# sensors.net
KiCad netlist of a schematic drawn in Altium Designer
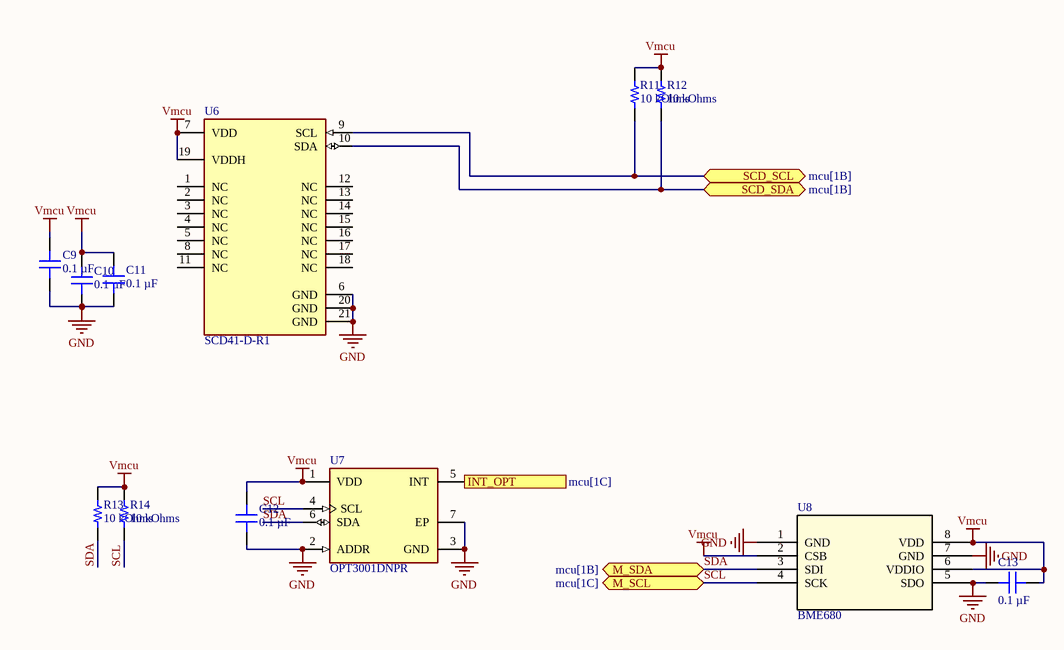
[diagram p0: sensors.SchDoc]

(export (version "E")
  (design (tool "Eeschema 10.0.6"))
  (components
    (comp (ref "C9")
      (value "0.1 µF")
      (footprint "CAP 0402_1005")
      (description "CAP CER 0.1UF 4V X5R 0402")
      (fields (field (name "PART NUMBER") "C0402C104K7PAC7867") (field (name "MANUFACTURER") "KEMET"))
      (libsource (lib "Celestial Altium Library - altium_library") (part "Capacitor"))
    )
    (comp (ref "C10")
      (value "0.1 µF")
      (footprint "CAP 0402_1005")
      (description "CAP CER 0.1UF 4V X5R 0402")
      (fields (field (name "PART NUMBER") "C0402C104K7PAC7867") (field (name "MANUFACTURER") "KEMET"))
      (libsource (lib "Celestial Altium Library - altium_library") (part "Capacitor"))
    )
    (comp (ref "C11")
      (value "0.1 µF")
      (footprint "CAP 0402_1005")
      (description "CAP CER 0.1UF 4V X5R 0402")
      (fields (field (name "PART NUMBER") "C0402C104K7PAC7867") (field (name "MANUFACTURER") "KEMET"))
      (libsource (lib "Celestial Altium Library - altium_library") (part "Capacitor"))
    )
    (comp (ref "C12")
      (value "0.1 µF")
      (footprint "CAP 0402_1005")
      (description "CAP CER 0.1UF 4V X5R 0402")
      (fields (field (name "PART NUMBER") "C0402C104K7PAC7867") (field (name "MANUFACTURER") "KEMET"))
      (libsource (lib "Celestial Altium Library - altium_library") (part "Capacitor"))
    )
    (comp (ref "C13")
      (value "0.1 µF")
      (footprint "CAP 0402_1005")
      (description "CAP CER 0.1UF 4V X5R 0402")
      (fields (field (name "PART NUMBER") "C0402C104K7PAC7867") (field (name "MANUFACTURER") "KEMET"))
      (libsource (lib "Celestial Altium Library - altium_library") (part "Capacitor"))
    )
    (comp (ref "R11")
      (value "10 kOhms")
      (footprint "RES 0402_1005")
      (description "RES 10K OHM 0.1% 1/10W 0402")
      (fields
        (field (name "PART NUMBER") "RP73PF1E10KBTD")
        (field (name "MANUFACTURER") "TE Connectivity Passive Product")
      )
      (libsource (lib "Celestial Altium Library - altium_library") (part "Resistor"))
    )
    (comp (ref "R12")
      (value "10 kOhms")
      (footprint "RES 0402_1005")
      (description "RES 10K OHM 0.1% 1/10W 0402")
      (fields
        (field (name "PART NUMBER") "RP73PF1E10KBTD")
        (field (name "MANUFACTURER") "TE Connectivity Passive Product")
      )
      (libsource (lib "Celestial Altium Library - altium_library") (part "Resistor"))
    )
    (comp (ref "R13")
      (value "10 kOhms")
      (footprint "RES 0402_1005")
      (description "RES 10K OHM 0.1% 1/10W 0402")
      (fields
        (field (name "PART NUMBER") "RP73PF1E10KBTD")
        (field (name "MANUFACTURER") "TE Connectivity Passive Product")
      )
      (libsource (lib "Celestial Altium Library - altium_library") (part "Resistor"))
    )
    (comp (ref "R14")
      (value "10 kOhms")
      (footprint "RES 0402_1005")
      (description "RES 10K OHM 0.1% 1/10W 0402")
      (fields
        (field (name "PART NUMBER") "RP73PF1E10KBTD")
        (field (name "MANUFACTURER") "TE Connectivity Passive Product")
      )
      (libsource (lib "Celestial Altium Library - altium_library") (part "Resistor"))
    )
    (comp (ref "U6")
      (value "SCD41-D-R1")
      (footprint "FP-SCD41-D-R1-MFG")
      (description "CO2 SENSOR 40 PPM I2C SMD")
      (libsource (lib "Altium Content Vault") (part "6ad75dfd843b95687531c15705827d7"))
    )
    (comp (ref "U7")
      (value "OPT3001DNPR")
      (footprint "FP-DNP0006A-MFG")
      (description "SENSOR OPT 550NM AMBIENT 6USON")
      (fields
        (field (name "OCTOPART") "https://octopart.com/opt3001dnpr-texas+instruments-47324050")
        (field (name "MANUFACTURER") "Texas Instruments")
      )
      (libsource (lib "Altium Content Vault") (part "6d36863dc75c3adee7e1b5a0d97a822"))
    )
    (comp (ref "U8")
      (value "BME680")
      (footprint "LGA8_BME680_BOS")
      (description "No Description Available")
      (libsource (lib "BME680") (part "BME680"))
    )
  )
  (nets
    (net (code "1") (name "/INT_OPT") (class "Default")
      (node (ref "U7") (pin "5") (pinfunction "INT_5") (pintype "open_collector"))
    )
    (net (code "2") (name "/SCD_SCL") (class "Default")
      (node (ref "R11") (pin "2") (pinfunction "2_2") (pintype "passive"))
      (node (ref "U6") (pin "9") (pinfunction "SCL_9") (pintype "input"))
    )
    (net (code "3") (name "/SCD_SDA") (class "Default")
      (node (ref "R12") (pin "2") (pinfunction "2_2") (pintype "passive"))
      (node (ref "U6") (pin "10") (pinfunction "SDA_10") (pintype "bidirectional"))
    )
    (net (code "4") (name "/SCL") (class "Default")
      (node (ref "R14") (pin "2") (pinfunction "2_2") (pintype "passive"))
      (node (ref "U7") (pin "4") (pinfunction "SCL_4") (pintype "input"))
      (node (ref "U8") (pin "4") (pinfunction "SCK_4") (pintype "passive"))
    )
    (net (code "5") (name "/SDA") (class "Default")
      (node (ref "R13") (pin "2") (pinfunction "2_2") (pintype "passive"))
      (node (ref "U7") (pin "6") (pinfunction "SDA_6") (pintype "bidirectional"))
      (node (ref "U8") (pin "3") (pinfunction "SDI_3") (pintype "passive"))
    )
    (net (code "6") (name "GND") (class "Default")
      (node (ref "C10") (pin "1") (pinfunction "1_1") (pintype "passive"))
      (node (ref "C11") (pin "1") (pinfunction "1_1") (pintype "passive"))
      (node (ref "C12") (pin "1") (pinfunction "1_1") (pintype "passive"))
      (node (ref "C13") (pin "2") (pinfunction "2_2") (pintype "passive"))
      (node (ref "C9") (pin "1") (pinfunction "1_1") (pintype "passive"))
      (node (ref "U6") (pin "20") (pinfunction "GND_20") (pintype "power_in"))
      (node (ref "U6") (pin "21") (pinfunction "GND_21") (pintype "power_in"))
      (node (ref "U6") (pin "6") (pinfunction "GND_6") (pintype "power_in"))
      (node (ref "U7") (pin "2") (pinfunction "ADDR_2") (pintype "input"))
      (node (ref "U7") (pin "3") (pinfunction "GND_3") (pintype "power_in"))
      (node (ref "U7") (pin "7") (pinfunction "EP_7") (pintype "power_in"))
      (node (ref "U8") (pin "1") (pinfunction "GND_1") (pintype "passive"))
      (node (ref "U8") (pin "5") (pinfunction "SDO_5") (pintype "passive"))
      (node (ref "U8") (pin "7") (pinfunction "GND_7") (pintype "passive"))
    )
    (net (code "7") (name "Vmcu") (class "Default")
      (node (ref "C10") (pin "2") (pinfunction "2_2") (pintype "passive"))
      (node (ref "C11") (pin "2") (pinfunction "2_2") (pintype "passive"))
      (node (ref "C12") (pin "2") (pinfunction "2_2") (pintype "passive"))
      (node (ref "C13") (pin "1") (pinfunction "1_1") (pintype "passive"))
      (node (ref "C9") (pin "2") (pinfunction "2_2") (pintype "passive"))
      (node (ref "R11") (pin "1") (pinfunction "1_1") (pintype "passive"))
      (node (ref "R12") (pin "1") (pinfunction "1_1") (pintype "passive"))
      (node (ref "R13") (pin "1") (pinfunction "1_1") (pintype "passive"))
      (node (ref "R14") (pin "1") (pinfunction "1_1") (pintype "passive"))
      (node (ref "U6") (pin "19") (pinfunction "VDDH_19") (pintype "power_in"))
      (node (ref "U6") (pin "7") (pinfunction "VDD_7") (pintype "power_in"))
      (node (ref "U7") (pin "1") (pinfunction "VDD_1") (pintype "power_in"))
      (node (ref "U8") (pin "2") (pinfunction "CSB_2") (pintype "passive"))
      (node (ref "U8") (pin "6") (pinfunction "VDDIO_6") (pintype "passive"))
      (node (ref "U8") (pin "8") (pinfunction "VDD_8") (pintype "passive"))
    )
    (net (code "8") (name "unconnected-(U6-NC-Pad1)") (class "Default")
      (node (ref "U6") (pin "1") (pinfunction "NC_1") (pintype "passive"))
    )
    (net (code "9") (name "unconnected-(U6-NC-Pad2)") (class "Default")
      (node (ref "U6") (pin "2") (pinfunction "NC_2") (pintype "passive"))
    )
    (net (code "10") (name "unconnected-(U6-NC-Pad3)") (class "Default")
      (node (ref "U6") (pin "3") (pinfunction "NC_3") (pintype "passive"))
    )
    (net (code "11") (name "unconnected-(U6-NC-Pad4)") (class "Default")
      (node (ref "U6") (pin "4") (pinfunction "NC_4") (pintype "passive"))
    )
    (net (code "12") (name "unconnected-(U6-NC-Pad5)") (class "Default")
      (node (ref "U6") (pin "5") (pinfunction "NC_5") (pintype "passive"))
    )
    (net (code "13") (name "unconnected-(U6-NC-Pad8)") (class "Default")
      (node (ref "U6") (pin "8") (pinfunction "NC_8") (pintype "passive"))
    )
    (net (code "14") (name "unconnected-(U6-NC-Pad11)") (class "Default")
      (node (ref "U6") (pin "11") (pinfunction "NC_11") (pintype "passive"))
    )
    (net (code "15") (name "unconnected-(U6-NC-Pad12)") (class "Default")
      (node (ref "U6") (pin "12") (pinfunction "NC_12") (pintype "passive"))
    )
    (net (code "16") (name "unconnected-(U6-NC-Pad13)") (class "Default")
      (node (ref "U6") (pin "13") (pinfunction "NC_13") (pintype "passive"))
    )
    (net (code "17") (name "unconnected-(U6-NC-Pad14)") (class "Default")
      (node (ref "U6") (pin "14") (pinfunction "NC_14") (pintype "passive"))
    )
    (net (code "18") (name "unconnected-(U6-NC-Pad15)") (class "Default")
      (node (ref "U6") (pin "15") (pinfunction "NC_15") (pintype "passive"))
    )
    (net (code "19") (name "unconnected-(U6-NC-Pad16)") (class "Default")
      (node (ref "U6") (pin "16") (pinfunction "NC_16") (pintype "passive"))
    )
    (net (code "20") (name "unconnected-(U6-NC-Pad17)") (class "Default")
      (node (ref "U6") (pin "17") (pinfunction "NC_17") (pintype "passive"))
    )
    (net (code "21") (name "unconnected-(U6-NC-Pad18)") (class "Default")
      (node (ref "U6") (pin "18") (pinfunction "NC_18") (pintype "passive"))
    )
  )
)
